# RepeterMySensorsXIAO.net
KiCad netlist of a schematic drawn in EAGLE
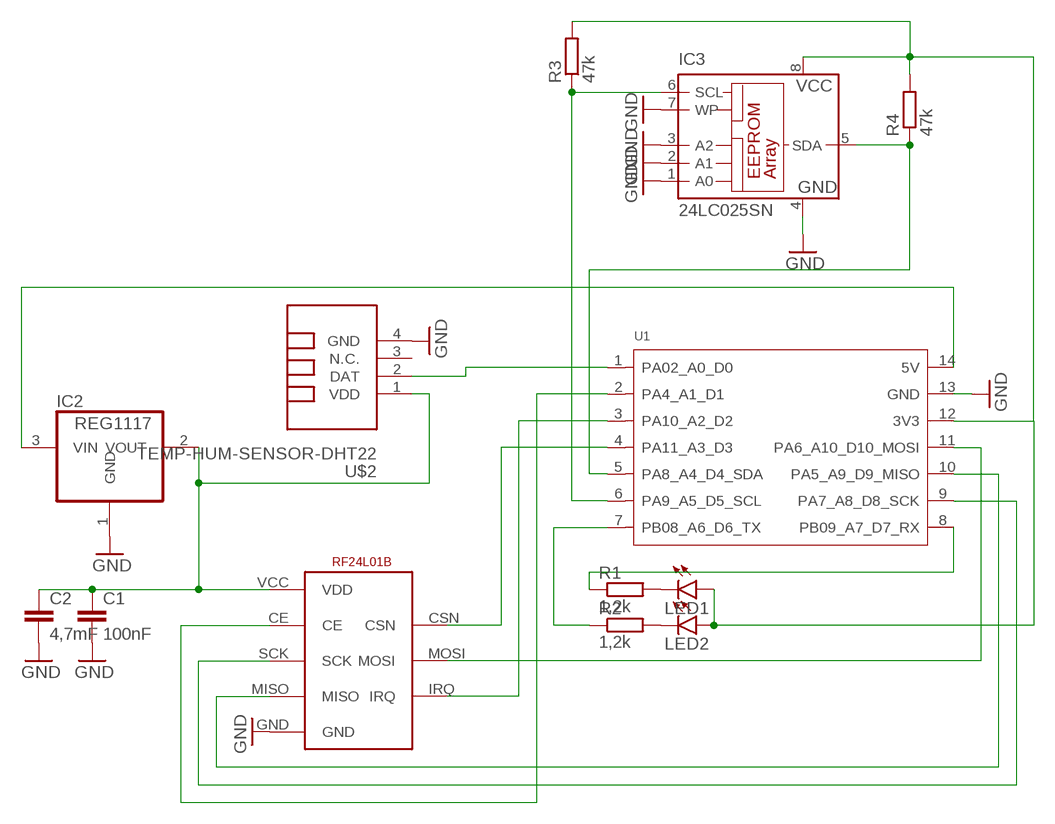
[diagram p0: schematic, sheet 1]

(export (version "E")
  (design (tool "Eeschema 10.0.6"))
  (components
    (comp (ref "C1")
      (value "100nF")
      (footprint "eagle-import:C1206")
      (libsource (lib "eagle-import") (part "C-EUC1206"))
    )
    (comp (ref "C2")
      (value "4,7mF")
      (footprint "eagle-import:C1210")
      (libsource (lib "eagle-import") (part "C-EUC1210"))
    )
    (comp (ref "IC2")
      (value "REG1117")
      (footprint "eagle-import:SOT223")
      (libsource (lib "eagle-import") (part "REG1117"))
    )
    (comp (ref "IC3")
      (value "24LC025SN")
      (footprint "eagle-import:SO-08")
      (fields (field (name "MF") "MICROCHIP") (field (name "MPN") "24LC025/SN"))
      (libsource (lib "eagle-import") (part "24SNLC025"))
    )
    (comp (ref "LED1")
      (value "LEDB152")
      (footprint "eagle-import:Q62902-B152")
      (libsource (lib "eagle-import") (part "LEDB152"))
    )
    (comp (ref "LED2")
      (value "LEDB152")
      (footprint "eagle-import:Q62902-B152")
      (libsource (lib "eagle-import") (part "LEDB152"))
    )
    (comp (ref "R1")
      (value "1,2k")
      (footprint "eagle-import:M1206")
      (libsource (lib "eagle-import") (part "R-EU_M1206"))
    )
    (comp (ref "R2")
      (value "1,2k")
      (footprint "eagle-import:M1206")
      (libsource (lib "eagle-import") (part "R-EU_M1206"))
    )
    (comp (ref "R3")
      (value "47k")
      (footprint "eagle-import:M1206")
      (libsource (lib "eagle-import") (part "R-EU_M1206"))
    )
    (comp (ref "R4")
      (value "47k")
      (footprint "eagle-import:M1206")
      (libsource (lib "eagle-import") (part "R-EU_M1206"))
    )
    (comp (ref "U$2")
      (value "TEMP-HUM-SENSOR-DHT22")
      (footprint "eagle-import:TEMP-HUM-SENSOR-DHT22")
      (libsource (lib "eagle-import") (part "TEMP-HUM-SENSOR-DHT22"))
    )
    (comp (ref "U$3")
      (value "NRF24L01EBYTE")
      (footprint "eagle-import:24L01EBYTE")
      (libsource (lib "eagle-import") (part "NRF24L01EBYTE"))
    )
    (comp (ref "U1")
      (value "MOUDLE-SEEEDUINO-XIAO")
      (footprint "eagle-import:MOUDLE14P-2.54-21X17.8MM")
      (libsource (lib "eagle-import") (part "MOUDLE-SEEEDUINO-XIAO"))
    )
  )
  (nets
    (net (code "1") (name "GND") (class "Default")
      (node (ref "C1") (pin "2") (pinfunction "2_2") (pintype "passive"))
      (node (ref "C2") (pin "2") (pinfunction "2_2") (pintype "passive"))
      (node (ref "IC2") (pin "1") (pinfunction "GND_1") (pintype "power_in"))
      (node (ref "IC3") (pin "1") (pinfunction "A0_1") (pintype "input"))
      (node (ref "IC3") (pin "2") (pinfunction "A1_2") (pintype "input"))
      (node (ref "IC3") (pin "3") (pinfunction "A2_3") (pintype "input"))
      (node (ref "IC3") (pin "4") (pinfunction "GND_4") (pintype "power_in"))
      (node (ref "IC3") (pin "7") (pinfunction "WP_7") (pintype "input"))
      (node (ref "U$2") (pin "4") (pinfunction "GND_4") (pintype "power_in"))
      (node (ref "U$3") (pin "GND") (pinfunction "GND_GND") (pintype "bidirectional"))
      (node (ref "U1") (pin "13") (pinfunction "GND_13") (pintype "bidirectional"))
    )
    (net (code "2") (name "Net-(IC2-VIN)") (class "Default")
      (node (ref "IC2") (pin "3") (pinfunction "VIN_3") (pintype "input"))
      (node (ref "U1") (pin "14") (pinfunction "5V_14") (pintype "bidirectional"))
    )
    (net (code "3") (name "Net-(IC2-VOUT)") (class "Default")
      (node (ref "C1") (pin "1") (pinfunction "1_1") (pintype "passive"))
      (node (ref "C2") (pin "1") (pinfunction "1_1") (pintype "passive"))
      (node (ref "IC2") (pin "2") (pinfunction "VOUT_2") (pintype "output"))
      (node (ref "U$2") (pin "1") (pinfunction "VDD_1") (pintype "power_in"))
      (node (ref "U$3") (pin "VCC") (pinfunction "VDD_VCC") (pintype "bidirectional"))
    )
    (net (code "4") (name "Net-(IC3-SCL)") (class "Default")
      (node (ref "IC3") (pin "6") (pinfunction "SCL_6") (pintype "input"))
      (node (ref "R3") (pin "1") (pinfunction "1_1") (pintype "passive"))
      (node (ref "U1") (pin "6") (pinfunction "PA9_A5_D5_SCL_6") (pintype "bidirectional"))
    )
    (net (code "5") (name "Net-(IC3-SDA)") (class "Default")
      (node (ref "IC3") (pin "5") (pinfunction "SDA_5") (pintype "bidirectional"))
      (node (ref "R4") (pin "1") (pinfunction "1_1") (pintype "passive"))
      (node (ref "U1") (pin "5") (pinfunction "PA8_A4_D4_SDA_5") (pintype "bidirectional"))
    )
    (net (code "6") (name "Net-(IC3-VCC)") (class "Default")
      (node (ref "IC3") (pin "8") (pinfunction "VCC_8") (pintype "power_in"))
      (node (ref "LED1") (pin "A") (pinfunction "A_A") (pintype "passive"))
      (node (ref "LED2") (pin "A") (pinfunction "A_A") (pintype "passive"))
      (node (ref "R3") (pin "2") (pinfunction "2_2") (pintype "passive"))
      (node (ref "R4") (pin "2") (pinfunction "2_2") (pintype "passive"))
      (node (ref "U1") (pin "12") (pinfunction "3V3_12") (pintype "bidirectional"))
    )
    (net (code "7") (name "Net-(LED1-C)") (class "Default")
      (node (ref "LED1") (pin "K") (pinfunction "C_K") (pintype "passive"))
      (node (ref "R1") (pin "2") (pinfunction "2_2") (pintype "passive"))
    )
    (net (code "8") (name "Net-(LED2-C)") (class "Default")
      (node (ref "LED2") (pin "K") (pinfunction "C_K") (pintype "passive"))
      (node (ref "R2") (pin "2") (pinfunction "2_2") (pintype "passive"))
    )
    (net (code "9") (name "Net-(U$2-DAT)") (class "Default")
      (node (ref "U$2") (pin "2") (pinfunction "DAT_2") (pintype "bidirectional"))
      (node (ref "U1") (pin "1") (pinfunction "PA02_A0_D0_1") (pintype "bidirectional"))
    )
    (net (code "10") (name "Net-(U1-PA4_A1_D1)") (class "Default")
      (node (ref "U$3") (pin "CE") (pinfunction "CE_CE") (pintype "bidirectional"))
      (node (ref "U1") (pin "2") (pinfunction "PA4_A1_D1_2") (pintype "bidirectional"))
    )
    (net (code "11") (name "Net-(U1-PA5_A9_D9_MISO)") (class "Default")
      (node (ref "U$3") (pin "MISO") (pinfunction "MISO_MISO") (pintype "bidirectional"))
      (node (ref "U1") (pin "10") (pinfunction "PA5_A9_D9_MISO_10") (pintype "bidirectional"))
    )
    (net (code "12") (name "Net-(U1-PA6_A10_D10_MOSI)") (class "Default")
      (node (ref "U$3") (pin "MOSI") (pinfunction "MOSI_MOSI") (pintype "bidirectional"))
      (node (ref "U1") (pin "11") (pinfunction "PA6_A10_D10_MOSI_11") (pintype "bidirectional"))
    )
    (net (code "13") (name "Net-(U1-PA7_A8_D8_SCK)") (class "Default")
      (node (ref "U$3") (pin "SCK") (pinfunction "SCK_SCK") (pintype "bidirectional"))
      (node (ref "U1") (pin "9") (pinfunction "PA7_A8_D8_SCK_9") (pintype "bidirectional"))
    )
    (net (code "14") (name "Net-(U1-PA10_A2_D2)") (class "Default")
      (node (ref "U$3") (pin "IRQ") (pinfunction "IRQ_IRQ") (pintype "bidirectional"))
      (node (ref "U1") (pin "3") (pinfunction "PA10_A2_D2_3") (pintype "bidirectional"))
    )
    (net (code "15") (name "Net-(U1-PA11_A3_D3)") (class "Default")
      (node (ref "U$3") (pin "CSN") (pinfunction "CSN_CSN") (pintype "bidirectional"))
      (node (ref "U1") (pin "4") (pinfunction "PA11_A3_D3_4") (pintype "bidirectional"))
    )
    (net (code "16") (name "Net-(U1-PB08_A6_D6_TX)") (class "Default")
      (node (ref "R2") (pin "1") (pinfunction "1_1") (pintype "passive"))
      (node (ref "U1") (pin "7") (pinfunction "PB08_A6_D6_TX_7") (pintype "bidirectional"))
    )
    (net (code "17") (name "Net-(U1-PB09_A7_D7_RX)") (class "Default")
      (node (ref "R1") (pin "1") (pinfunction "1_1") (pintype "passive"))
      (node (ref "U1") (pin "8") (pinfunction "PB09_A7_D7_RX_8") (pintype "bidirectional"))
    )
    (net (code "18") (name "unconnected-(U$2-N.C.-Pad3)") (class "Default")
      (node (ref "U$2") (pin "3") (pinfunction "N.C._3") (pintype "passive"))
    )
  )
)
